# power.net
KiCad netlist of a schematic drawn in Altium Designer
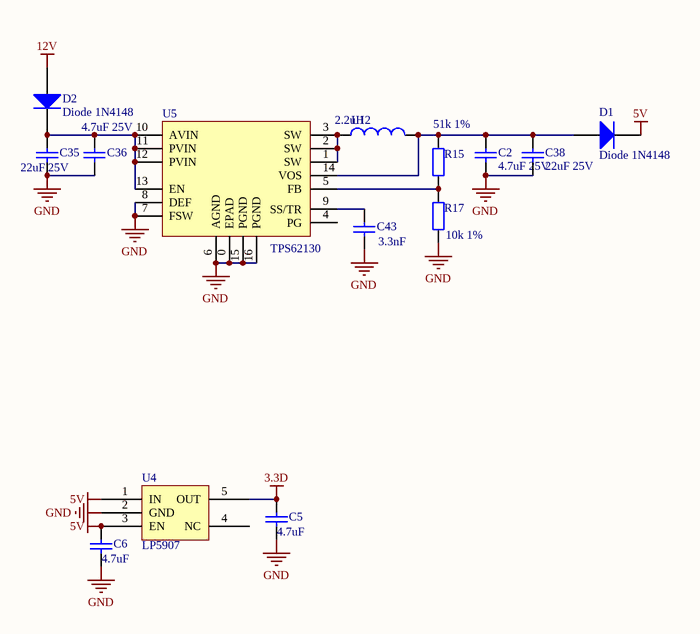
[diagram p0: power.SchDoc]

(export (version "E")
  (design (tool "Eeschema 10.0.6"))
  (components
    (comp (ref "C2")
      (value "4.7uF 25V")
      (footprint "0603")
      (description "Capacitor")
      (fields (field (name "Comment") "Cap") (field (name "PUBLISHER") "Altium Limited"))
      (libsource (lib "RTC6705") (part "Cap"))
    )
    (comp (ref "C5")
      (value "4.7uF")
      (footprint "0603L")
      (description "Capacitor")
      (fields (field (name "PUBLISHER") "Altium Limited"))
      (libsource (lib "RTC6705") (part "Cap"))
    )
    (comp (ref "C6")
      (value "4.7uF")
      (footprint "0603L")
      (description "Capacitor")
      (fields (field (name "PUBLISHER") "Altium Limited"))
      (libsource (lib "RTC6705") (part "Cap"))
    )
    (comp (ref "C35")
      (value "22uF 25V")
      (footprint "0805")
      (description "Capacitor")
      (fields (field (name "Comment") "Cap") (field (name "PUBLISHER") "Altium Limited"))
      (libsource (lib "RTC6705") (part "Cap"))
    )
    (comp (ref "C36")
      (value "4.7uF 25V")
      (footprint "0603")
      (description "Capacitor")
      (fields (field (name "Comment") "Cap") (field (name "PUBLISHER") "Altium Limited"))
      (libsource (lib "RTC6705") (part "Cap"))
    )
    (comp (ref "C38")
      (value "22uF 25V")
      (footprint "0805")
      (description "Capacitor")
      (fields (field (name "Comment") "Cap") (field (name "PUBLISHER") "Altium Limited"))
      (libsource (lib "RTC6705") (part "Cap"))
    )
    (comp (ref "C43")
      (value "3.3nF")
      (footprint "0402")
      (description "Capacitor")
      (fields (field (name "PUBLISHER") "Altium Limited"))
      (libsource (lib "RTC6705") (part "Cap"))
    )
    (comp (ref "D1")
      (value "Diode 1N4148")
      (footprint "LC-SOD-323")
      (description "High Conductance Fast Diode")
      (fields (field (name "PUBLISHER") "Altium Limited"))
      (libsource (lib "Miscellaneous Devices") (part "Diode 1N4148"))
    )
    (comp (ref "D2")
      (value "Diode 1N4148")
      (footprint "LC-SOD-323")
      (description "High Conductance Fast Diode")
      (fields (field (name "PUBLISHER") "Altium Limited"))
      (libsource (lib "Miscellaneous Devices") (part "Diode 1N4148"))
    )
    (comp (ref "L12")
      (value "2.2uH")
      (footprint "L4015")
      (description "Inductor")
      (fields (field (name "PUBLISHER") "Altium Limited"))
      (libsource (lib "Miscellaneous Devices") (part "Inductor"))
    )
    (comp (ref "R15")
      (value "51k 1%")
      (footprint "0402")
      (description "Resistor")
      (fields (field (name "PUBLISHER") "Altium Limited"))
      (libsource (lib "RTC6705") (part "Res2"))
    )
    (comp (ref "R17")
      (value "10k 1%")
      (footprint "0402")
      (description "Resistor")
      (fields (field (name "PUBLISHER") "Altium Limited"))
      (libsource (lib "RTC6705") (part "Res2"))
    )
    (comp (ref "U4") (value "LP5907") (footprint "SOT23-5") (libsource (lib "RTC6705") (part "LP5907")))
    (comp (ref "U5") (value "TPS62130") (footprint "TPS62130") (libsource (lib "sch") (part "TPS62130")))
  )
  (nets
    (net (code "1") (name "3.3D") (class "Default")
      (node (ref "C5") (pin "2") (pinfunction "2_2") (pintype "passive"))
      (node (ref "U4") (pin "5") (pinfunction "OUT_5") (pintype "passive"))
    )
    (net (code "2") (name "5V") (class "Default")
      (node (ref "C6") (pin "2") (pinfunction "2_2") (pintype "passive"))
      (node (ref "D1") (pin "2") (pinfunction "K_2") (pintype "passive"))
      (node (ref "U4") (pin "1") (pinfunction "IN_1") (pintype "passive"))
      (node (ref "U4") (pin "3") (pinfunction "EN_3") (pintype "passive"))
    )
    (net (code "3") (name "12V") (class "Default")
      (node (ref "D2") (pin "1") (pinfunction "A_1") (pintype "passive"))
    )
    (net (code "4") (name "GND") (class "Default")
      (node (ref "C2") (pin "1") (pinfunction "1_1") (pintype "passive"))
      (node (ref "C35") (pin "2") (pinfunction "2_2") (pintype "passive"))
      (node (ref "C36") (pin "2") (pinfunction "2_2") (pintype "passive"))
      (node (ref "C38") (pin "1") (pinfunction "1_1") (pintype "passive"))
      (node (ref "C43") (pin "2") (pinfunction "2_2") (pintype "passive"))
      (node (ref "C5") (pin "1") (pinfunction "1_1") (pintype "passive"))
      (node (ref "C6") (pin "1") (pinfunction "1_1") (pintype "passive"))
      (node (ref "R17") (pin "2") (pinfunction "2_2") (pintype "passive"))
      (node (ref "U4") (pin "2") (pinfunction "GND_2") (pintype "passive"))
      (node (ref "U5") (pin "0") (pinfunction "EPAD_0") (pintype "passive"))
      (node (ref "U5") (pin "15") (pinfunction "PGND_15") (pintype "passive"))
      (node (ref "U5") (pin "16") (pinfunction "PGND_16") (pintype "passive"))
      (node (ref "U5") (pin "6") (pinfunction "AGND_6") (pintype "passive"))
      (node (ref "U5") (pin "7") (pinfunction "FSW_7") (pintype "passive"))
      (node (ref "U5") (pin "8") (pinfunction "DEF_8") (pintype "passive"))
    )
    (net (code "5") (name "Net-(D1-A)") (class "Default")
      (node (ref "C2") (pin "2") (pinfunction "2_2") (pintype "passive"))
      (node (ref "C38") (pin "2") (pinfunction "2_2") (pintype "passive"))
      (node (ref "D1") (pin "1") (pinfunction "A_1") (pintype "passive"))
      (node (ref "L12") (pin "2") (pinfunction "2_2") (pintype "passive"))
      (node (ref "R15") (pin "1") (pinfunction "1_1") (pintype "passive"))
      (node (ref "U5") (pin "14") (pinfunction "VOS_14") (pintype "passive"))
    )
    (net (code "6") (name "Net-(D2-K)") (class "Default")
      (node (ref "C35") (pin "1") (pinfunction "1_1") (pintype "passive"))
      (node (ref "C36") (pin "1") (pinfunction "1_1") (pintype "passive"))
      (node (ref "D2") (pin "2") (pinfunction "K_2") (pintype "passive"))
      (node (ref "U5") (pin "10") (pinfunction "AVIN_10") (pintype "passive"))
      (node (ref "U5") (pin "11") (pinfunction "PVIN_11") (pintype "passive"))
      (node (ref "U5") (pin "12") (pinfunction "PVIN_12") (pintype "passive"))
      (node (ref "U5") (pin "13") (pinfunction "EN_13") (pintype "passive"))
    )
    (net (code "7") (name "Net-(L12-Pad1)") (class "Default")
      (node (ref "L12") (pin "1") (pinfunction "1_1") (pintype "passive"))
      (node (ref "U5") (pin "1") (pinfunction "SW_1") (pintype "passive"))
      (node (ref "U5") (pin "2") (pinfunction "SW_2") (pintype "passive"))
      (node (ref "U5") (pin "3") (pinfunction "SW_3") (pintype "passive"))
    )
    (net (code "8") (name "Net-(U5-FB)") (class "Default")
      (node (ref "R15") (pin "2") (pinfunction "2_2") (pintype "passive"))
      (node (ref "R17") (pin "1") (pinfunction "1_1") (pintype "passive"))
      (node (ref "U5") (pin "5") (pinfunction "FB_5") (pintype "passive"))
    )
    (net (code "9") (name "Net-(U5-SS{slash}TR)") (class "Default")
      (node (ref "C43") (pin "1") (pinfunction "1_1") (pintype "passive"))
      (node (ref "U5") (pin "9") (pinfunction "SS/TR_9") (pintype "passive"))
    )
    (net (code "10") (name "unconnected-(U4-NC-Pad4)") (class "Default")
      (node (ref "U4") (pin "4") (pinfunction "NC_4") (pintype "passive"))
    )
    (net (code "11") (name "unconnected-(U5-PG-Pad4)") (class "Default")
      (node (ref "U5") (pin "4") (pinfunction "PG_4") (pintype "passive"))
    )
  )
)
